# Head_Lamp.net
KiCad netlist of a schematic drawn in EAGLE
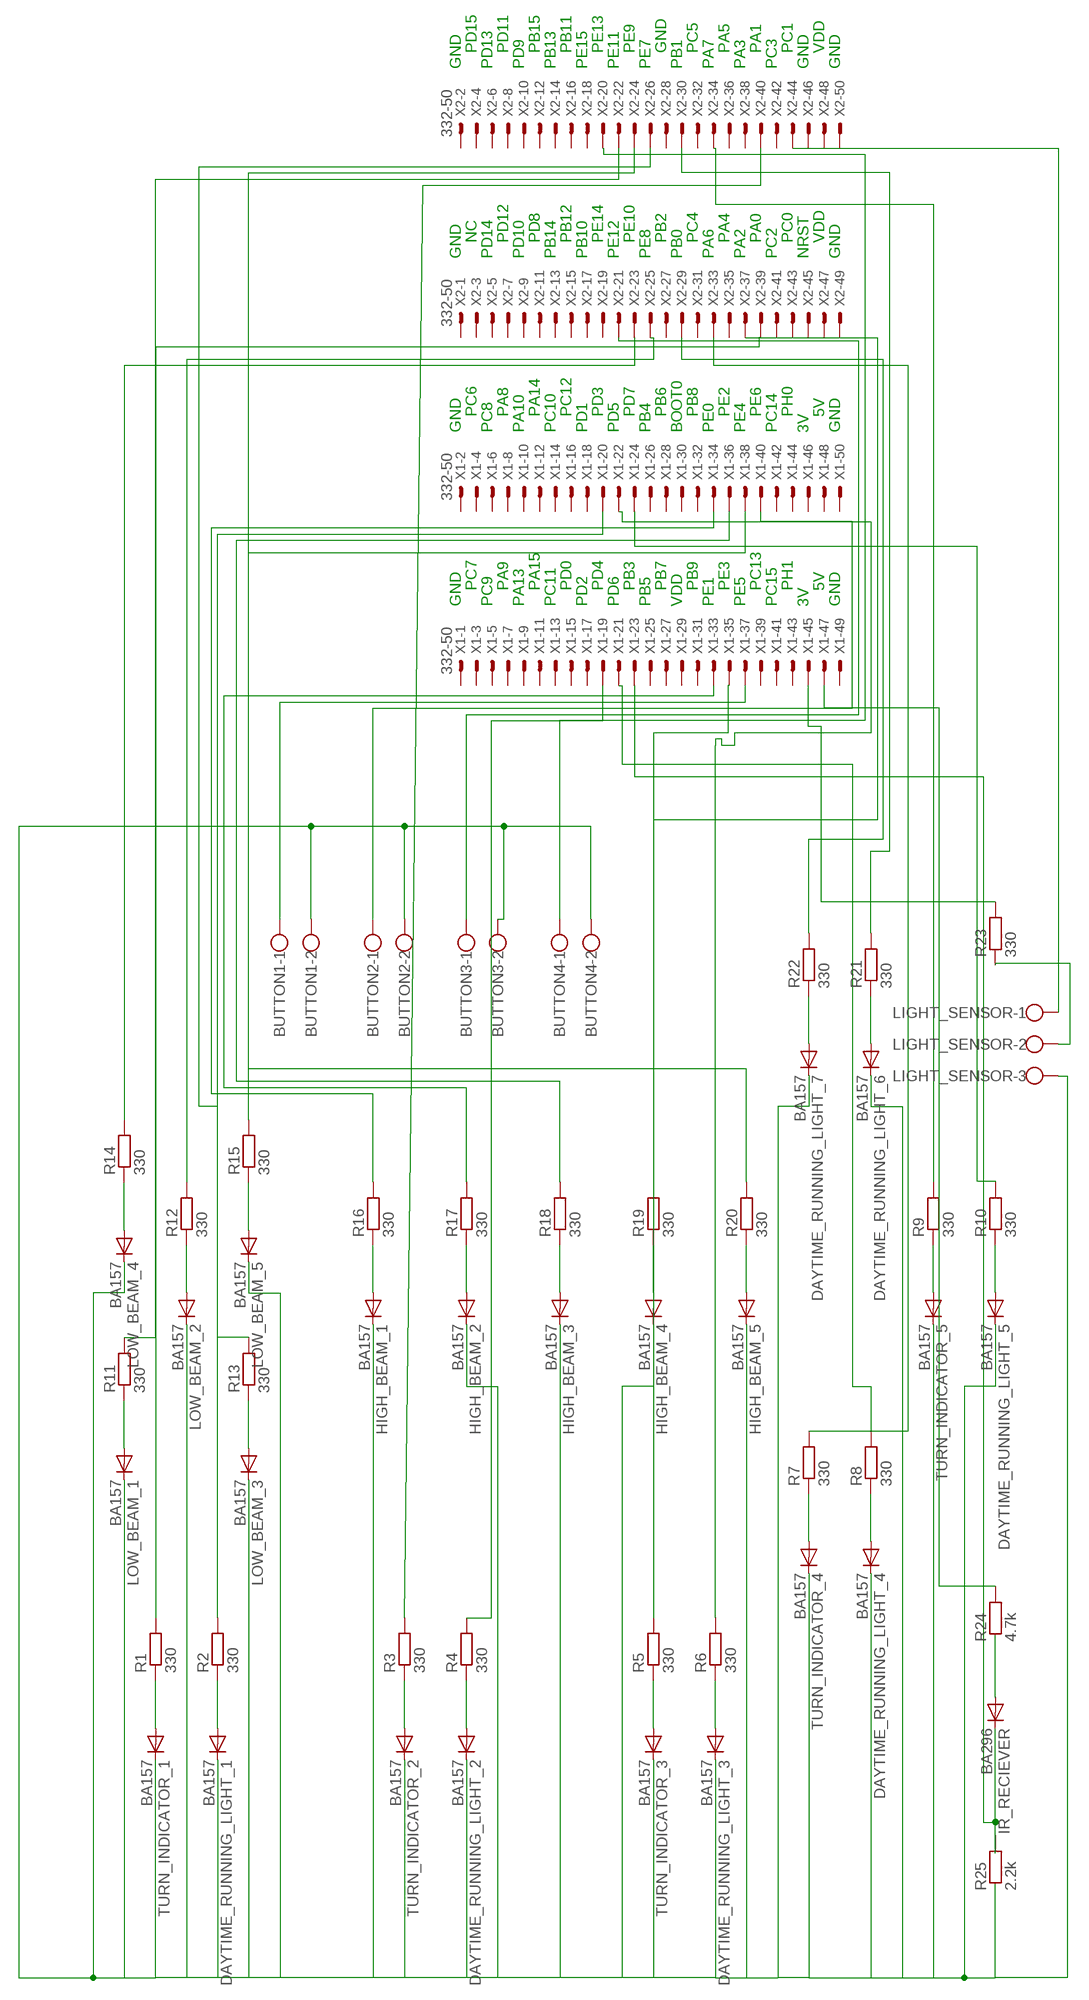
[diagram p0: schematic, sheet 1]

(export (version "E")
  (design (tool "Eeschema 10.0.6"))
  (components
    (comp (ref "BUTTON1")
      (value "W237-102")
      (footprint "eagle-import:W237-102")
      (fields (field (name "MPN") "237-102"))
      (libsource (lib "eagle-import") (part "W237-102"))
    )
    (comp (ref "BUTTON2")
      (value "W237-102")
      (footprint "eagle-import:W237-102")
      (fields (field (name "MPN") "237-102"))
      (libsource (lib "eagle-import") (part "W237-102"))
    )
    (comp (ref "BUTTON3")
      (value "W237-102")
      (footprint "eagle-import:W237-102")
      (fields (field (name "MPN") "237-102"))
      (libsource (lib "eagle-import") (part "W237-102"))
    )
    (comp (ref "BUTTON4")
      (value "W237-102")
      (footprint "eagle-import:W237-102")
      (fields (field (name "MPN") "237-102"))
      (libsource (lib "eagle-import") (part "W237-102"))
    )
    (comp (ref "DAYTIME_RUNNING_LIGHT_1")
      (value "BA157")
      (footprint "eagle-import:P1-10")
      (libsource (lib "eagle-import") (part "BA157"))
    )
    (comp (ref "DAYTIME_RUNNING_LIGHT_2")
      (value "BA157")
      (footprint "eagle-import:P1-10")
      (libsource (lib "eagle-import") (part "BA157"))
    )
    (comp (ref "DAYTIME_RUNNING_LIGHT_3")
      (value "BA157")
      (footprint "eagle-import:P1-10")
      (libsource (lib "eagle-import") (part "BA157"))
    )
    (comp (ref "DAYTIME_RUNNING_LIGHT_4")
      (value "BA157")
      (footprint "eagle-import:P1-10")
      (libsource (lib "eagle-import") (part "BA157"))
    )
    (comp (ref "DAYTIME_RUNNING_LIGHT_5")
      (value "BA157")
      (footprint "eagle-import:P1-10")
      (libsource (lib "eagle-import") (part "BA157"))
    )
    (comp (ref "DAYTIME_RUNNING_LIGHT_6")
      (value "BA157")
      (footprint "eagle-import:P1-10")
      (libsource (lib "eagle-import") (part "BA157"))
    )
    (comp (ref "DAYTIME_RUNNING_LIGHT_7")
      (value "BA157")
      (footprint "eagle-import:P1-10")
      (libsource (lib "eagle-import") (part "BA157"))
    )
    (comp (ref "HIGH_BEAM_1")
      (value "BA157")
      (footprint "eagle-import:P1-10")
      (libsource (lib "eagle-import") (part "BA157"))
    )
    (comp (ref "HIGH_BEAM_2")
      (value "BA157")
      (footprint "eagle-import:P1-10")
      (libsource (lib "eagle-import") (part "BA157"))
    )
    (comp (ref "HIGH_BEAM_3")
      (value "BA157")
      (footprint "eagle-import:P1-10")
      (libsource (lib "eagle-import") (part "BA157"))
    )
    (comp (ref "HIGH_BEAM_4")
      (value "BA157")
      (footprint "eagle-import:P1-10")
      (libsource (lib "eagle-import") (part "BA157"))
    )
    (comp (ref "HIGH_BEAM_5")
      (value "BA157")
      (footprint "eagle-import:P1-10")
      (libsource (lib "eagle-import") (part "BA157"))
    )
    (comp (ref "IR_RECIEVER")
      (value "BA296")
      (footprint "eagle-import:P2-15")
      (libsource (lib "eagle-import") (part "BA296"))
    )
    (comp (ref "LIGHT_SENSOR")
      (value "W237-103")
      (footprint "eagle-import:W237-103")
      (fields (field (name "MPN") "237-103"))
      (libsource (lib "eagle-import") (part "W237-103"))
    )
    (comp (ref "LOW_BEAM_1")
      (value "BA157")
      (footprint "eagle-import:P1-10")
      (libsource (lib "eagle-import") (part "BA157"))
    )
    (comp (ref "LOW_BEAM_2")
      (value "BA157")
      (footprint "eagle-import:P1-10")
      (libsource (lib "eagle-import") (part "BA157"))
    )
    (comp (ref "LOW_BEAM_3")
      (value "BA157")
      (footprint "eagle-import:P1-10")
      (libsource (lib "eagle-import") (part "BA157"))
    )
    (comp (ref "LOW_BEAM_4")
      (value "BA157")
      (footprint "eagle-import:P1-10")
      (libsource (lib "eagle-import") (part "BA157"))
    )
    (comp (ref "LOW_BEAM_5")
      (value "BA157")
      (footprint "eagle-import:P1-10")
      (libsource (lib "eagle-import") (part "BA157"))
    )
    (comp (ref "R1")
      (value "330")
      (footprint "eagle-import:0204_7")
      (libsource (lib "eagle-import") (part "R0204/7"))
    )
    (comp (ref "R2")
      (value "330")
      (footprint "eagle-import:0204_7")
      (libsource (lib "eagle-import") (part "R0204/7"))
    )
    (comp (ref "R3")
      (value "330")
      (footprint "eagle-import:0204_7")
      (libsource (lib "eagle-import") (part "R0204/7"))
    )
    (comp (ref "R4")
      (value "330")
      (footprint "eagle-import:0204_7")
      (libsource (lib "eagle-import") (part "R0204/7"))
    )
    (comp (ref "R5")
      (value "330")
      (footprint "eagle-import:0204_7")
      (libsource (lib "eagle-import") (part "R0204/7"))
    )
    (comp (ref "R6")
      (value "330")
      (footprint "eagle-import:0204_7")
      (libsource (lib "eagle-import") (part "R0204/7"))
    )
    (comp (ref "R7")
      (value "330")
      (footprint "eagle-import:0204_7")
      (libsource (lib "eagle-import") (part "R0204/7"))
    )
    (comp (ref "R8")
      (value "330")
      (footprint "eagle-import:0204_7")
      (libsource (lib "eagle-import") (part "R0204/7"))
    )
    (comp (ref "R9")
      (value "330")
      (footprint "eagle-import:0204_7")
      (libsource (lib "eagle-import") (part "R0204/7"))
    )
    (comp (ref "R10")
      (value "330")
      (footprint "eagle-import:0204_7")
      (libsource (lib "eagle-import") (part "R0204/7"))
    )
    (comp (ref "R11")
      (value "330")
      (footprint "eagle-import:0204_7")
      (libsource (lib "eagle-import") (part "R0204/7"))
    )
    (comp (ref "R12")
      (value "330")
      (footprint "eagle-import:0204_7")
      (libsource (lib "eagle-import") (part "R0204/7"))
    )
    (comp (ref "R13")
      (value "330")
      (footprint "eagle-import:0204_7")
      (libsource (lib "eagle-import") (part "R0204/7"))
    )
    (comp (ref "R14")
      (value "330")
      (footprint "eagle-import:0204_7")
      (libsource (lib "eagle-import") (part "R0204/7"))
    )
    (comp (ref "R15")
      (value "330")
      (footprint "eagle-import:0204_7")
      (libsource (lib "eagle-import") (part "R0204/7"))
    )
    (comp (ref "R16")
      (value "330")
      (footprint "eagle-import:0204_7")
      (libsource (lib "eagle-import") (part "R0204/7"))
    )
    (comp (ref "R17")
      (value "330")
      (footprint "eagle-import:0204_7")
      (libsource (lib "eagle-import") (part "R0204/7"))
    )
    (comp (ref "R18")
      (value "330")
      (footprint "eagle-import:0204_7")
      (libsource (lib "eagle-import") (part "R0204/7"))
    )
    (comp (ref "R19")
      (value "330")
      (footprint "eagle-import:0204_7")
      (libsource (lib "eagle-import") (part "R0204/7"))
    )
    (comp (ref "R20")
      (value "330")
      (footprint "eagle-import:0204_7")
      (libsource (lib "eagle-import") (part "R0204/7"))
    )
    (comp (ref "R21")
      (value "330")
      (footprint "eagle-import:0204_7")
      (libsource (lib "eagle-import") (part "R0204/7"))
    )
    (comp (ref "R22")
      (value "330")
      (footprint "eagle-import:0204_7")
      (libsource (lib "eagle-import") (part "R0204/7"))
    )
    (comp (ref "R23")
      (value "330")
      (footprint "eagle-import:0204_7")
      (libsource (lib "eagle-import") (part "R0204/7"))
    )
    (comp (ref "R24")
      (value "4.7k")
      (footprint "eagle-import:0204_7")
      (libsource (lib "eagle-import") (part "R0204/7"))
    )
    (comp (ref "R25")
      (value "2.2k")
      (footprint "eagle-import:0204_7")
      (libsource (lib "eagle-import") (part "R0204/7"))
    )
    (comp (ref "TURN_INDICATOR_1")
      (value "BA157")
      (footprint "eagle-import:P1-10")
      (libsource (lib "eagle-import") (part "BA157"))
    )
    (comp (ref "TURN_INDICATOR_2")
      (value "BA157")
      (footprint "eagle-import:P1-10")
      (libsource (lib "eagle-import") (part "BA157"))
    )
    (comp (ref "TURN_INDICATOR_3")
      (value "BA157")
      (footprint "eagle-import:P1-10")
      (libsource (lib "eagle-import") (part "BA157"))
    )
    (comp (ref "TURN_INDICATOR_4")
      (value "BA157")
      (footprint "eagle-import:P1-10")
      (libsource (lib "eagle-import") (part "BA157"))
    )
    (comp (ref "TURN_INDICATOR_5")
      (value "BA157")
      (footprint "eagle-import:P1-10")
      (libsource (lib "eagle-import") (part "BA157"))
    )
    (comp (ref "X1")
      (value "332-50")
      (footprint "eagle-import:332-50")
      (libsource (lib "eagle-import") (part "332-50"))
    )
    (comp (ref "X2")
      (value "332-50")
      (footprint "eagle-import:332-50")
      (libsource (lib "eagle-import") (part "332-50"))
    )
  )
  (nets
    (net (code "1") (name "Net-(BUTTON1A-KL)") (class "Default")
      (node (ref "BUTTON1") (pin "1") (pinfunction "KL_1") (pintype "passive"))
      (node (ref "X1") (pin "37") (pinfunction "S_37") (pintype "passive"))
    )
    (net (code "2") (name "Net-(BUTTON1B-KL)") (class "Default")
      (node (ref "BUTTON1") (pin "2") (pinfunction "KL_2") (pintype "passive"))
      (node (ref "BUTTON2") (pin "2") (pinfunction "KL_2") (pintype "passive"))
      (node (ref "BUTTON3") (pin "2") (pinfunction "KL_2") (pintype "passive"))
      (node (ref "BUTTON4") (pin "2") (pinfunction "KL_2") (pintype "passive"))
      (node (ref "DAYTIME_RUNNING_LIGHT_1") (pin "C") (pinfunction "C_C") (pintype "passive"))
      (node (ref "DAYTIME_RUNNING_LIGHT_2") (pin "C") (pinfunction "C_C") (pintype "passive"))
      (node (ref "DAYTIME_RUNNING_LIGHT_3") (pin "C") (pinfunction "C_C") (pintype "passive"))
      (node (ref "DAYTIME_RUNNING_LIGHT_4") (pin "C") (pinfunction "C_C") (pintype "passive"))
      (node (ref "DAYTIME_RUNNING_LIGHT_5") (pin "C") (pinfunction "C_C") (pintype "passive"))
      (node (ref "DAYTIME_RUNNING_LIGHT_6") (pin "C") (pinfunction "C_C") (pintype "passive"))
      (node (ref "DAYTIME_RUNNING_LIGHT_7") (pin "C") (pinfunction "C_C") (pintype "passive"))
      (node (ref "HIGH_BEAM_1") (pin "C") (pinfunction "C_C") (pintype "passive"))
      (node (ref "HIGH_BEAM_2") (pin "C") (pinfunction "C_C") (pintype "passive"))
      (node (ref "HIGH_BEAM_3") (pin "C") (pinfunction "C_C") (pintype "passive"))
      (node (ref "HIGH_BEAM_4") (pin "C") (pinfunction "C_C") (pintype "passive"))
      (node (ref "HIGH_BEAM_5") (pin "C") (pinfunction "C_C") (pintype "passive"))
      (node (ref "LIGHT_SENSOR") (pin "3") (pinfunction "KL_3") (pintype "passive"))
      (node (ref "LOW_BEAM_1") (pin "C") (pinfunction "C_C") (pintype "passive"))
      (node (ref "LOW_BEAM_2") (pin "C") (pinfunction "C_C") (pintype "passive"))
      (node (ref "LOW_BEAM_3") (pin "C") (pinfunction "C_C") (pintype "passive"))
      (node (ref "LOW_BEAM_4") (pin "C") (pinfunction "C_C") (pintype "passive"))
      (node (ref "LOW_BEAM_5") (pin "C") (pinfunction "C_C") (pintype "passive"))
      (node (ref "TURN_INDICATOR_1") (pin "C") (pinfunction "C_C") (pintype "passive"))
      (node (ref "TURN_INDICATOR_2") (pin "C") (pinfunction "C_C") (pintype "passive"))
      (node (ref "TURN_INDICATOR_3") (pin "C") (pinfunction "C_C") (pintype "passive"))
      (node (ref "TURN_INDICATOR_4") (pin "C") (pinfunction "C_C") (pintype "passive"))
      (node (ref "TURN_INDICATOR_5") (pin "C") (pinfunction "C_C") (pintype "passive"))
    )
    (net (code "3") (name "Net-(BUTTON2A-KL)") (class "Default")
      (node (ref "BUTTON2") (pin "1") (pinfunction "KL_1") (pintype "passive"))
      (node (ref "X1") (pin "40") (pinfunction "S_40") (pintype "passive"))
    )
    (net (code "4") (name "Net-(BUTTON3A-KL)") (class "Default")
      (node (ref "BUTTON3") (pin "1") (pinfunction "KL_1") (pintype "passive"))
      (node (ref "X2") (pin "21") (pinfunction "S_21") (pintype "passive"))
    )
    (net (code "5") (name "Net-(BUTTON4A-KL)") (class "Default")
      (node (ref "BUTTON4") (pin "1") (pinfunction "KL_1") (pintype "passive"))
      (node (ref "X2") (pin "20") (pinfunction "S_20") (pintype "passive"))
    )
    (net (code "6") (name "Net-(DAYTIME_RUNNING_LIGHT_1-PadA)") (class "Default")
      (node (ref "DAYTIME_RUNNING_LIGHT_1") (pin "A") (pinfunction "A_A") (pintype "passive"))
      (node (ref "R2") (pin "1") (pinfunction "1_1") (pintype "passive"))
    )
    (net (code "7") (name "Net-(DAYTIME_RUNNING_LIGHT_2-PadA)") (class "Default")
      (node (ref "DAYTIME_RUNNING_LIGHT_2") (pin "A") (pinfunction "A_A") (pintype "passive"))
      (node (ref "R4") (pin "1") (pinfunction "1_1") (pintype "passive"))
    )
    (net (code "8") (name "Net-(DAYTIME_RUNNING_LIGHT_3-PadA)") (class "Default")
      (node (ref "DAYTIME_RUNNING_LIGHT_3") (pin "A") (pinfunction "A_A") (pintype "passive"))
      (node (ref "R6") (pin "1") (pinfunction "1_1") (pintype "passive"))
    )
    (net (code "9") (name "Net-(DAYTIME_RUNNING_LIGHT_4-PadA)") (class "Default")
      (node (ref "DAYTIME_RUNNING_LIGHT_4") (pin "A") (pinfunction "A_A") (pintype "passive"))
      (node (ref "R8") (pin "1") (pinfunction "1_1") (pintype "passive"))
    )
    (net (code "10") (name "Net-(DAYTIME_RUNNING_LIGHT_5-PadA)") (class "Default")
      (node (ref "DAYTIME_RUNNING_LIGHT_5") (pin "A") (pinfunction "A_A") (pintype "passive"))
      (node (ref "R10") (pin "1") (pinfunction "1_1") (pintype "passive"))
    )
    (net (code "11") (name "Net-(DAYTIME_RUNNING_LIGHT_6-PadA)") (class "Default")
      (node (ref "DAYTIME_RUNNING_LIGHT_6") (pin "A") (pinfunction "A_A") (pintype "passive"))
      (node (ref "R21") (pin "1") (pinfunction "1_1") (pintype "passive"))
    )
    (net (code "12") (name "Net-(DAYTIME_RUNNING_LIGHT_7-PadA)") (class "Default")
      (node (ref "DAYTIME_RUNNING_LIGHT_7") (pin "A") (pinfunction "A_A") (pintype "passive"))
      (node (ref "R22") (pin "1") (pinfunction "1_1") (pintype "passive"))
    )
    (net (code "13") (name "Net-(HIGH_BEAM_1-PadA)") (class "Default")
      (node (ref "HIGH_BEAM_1") (pin "A") (pinfunction "A_A") (pintype "passive"))
      (node (ref "R16") (pin "1") (pinfunction "1_1") (pintype "passive"))
    )
    (net (code "14") (name "Net-(HIGH_BEAM_2-PadA)") (class "Default")
      (node (ref "HIGH_BEAM_2") (pin "A") (pinfunction "A_A") (pintype "passive"))
      (node (ref "R17") (pin "1") (pinfunction "1_1") (pintype "passive"))
    )
    (net (code "15") (name "Net-(HIGH_BEAM_3-PadA)") (class "Default")
      (node (ref "HIGH_BEAM_3") (pin "A") (pinfunction "A_A") (pintype "passive"))
      (node (ref "R18") (pin "1") (pinfunction "1_1") (pintype "passive"))
    )
    (net (code "16") (name "Net-(HIGH_BEAM_4-PadA)") (class "Default")
      (node (ref "HIGH_BEAM_4") (pin "A") (pinfunction "A_A") (pintype "passive"))
      (node (ref "R19") (pin "1") (pinfunction "1_1") (pintype "passive"))
    )
    (net (code "17") (name "Net-(HIGH_BEAM_5-PadA)") (class "Default")
      (node (ref "HIGH_BEAM_5") (pin "A") (pinfunction "A_A") (pintype "passive"))
      (node (ref "R20") (pin "1") (pinfunction "1_1") (pintype "passive"))
    )
    (net (code "18") (name "Net-(LIGHT_SENSORA-KL)") (class "Default")
      (node (ref "LIGHT_SENSOR") (pin "1") (pinfunction "KL_1") (pintype "passive"))
      (node (ref "X2") (pin "44") (pinfunction "S_44") (pintype "passive"))
    )
    (net (code "19") (name "Net-(LIGHT_SENSORB-KL)") (class "Default")
      (node (ref "LIGHT_SENSOR") (pin "2") (pinfunction "KL_2") (pintype "passive"))
      (node (ref "R23") (pin "1") (pinfunction "1_1") (pintype "passive"))
    )
    (net (code "20") (name "Net-(LOW_BEAM_1-PadA)") (class "Default")
      (node (ref "LOW_BEAM_1") (pin "A") (pinfunction "A_A") (pintype "passive"))
      (node (ref "R11") (pin "1") (pinfunction "1_1") (pintype "passive"))
    )
    (net (code "21") (name "Net-(LOW_BEAM_2-PadA)") (class "Default")
      (node (ref "LOW_BEAM_2") (pin "A") (pinfunction "A_A") (pintype "passive"))
      (node (ref "R12") (pin "1") (pinfunction "1_1") (pintype "passive"))
    )
    (net (code "22") (name "Net-(LOW_BEAM_3-PadA)") (class "Default")
      (node (ref "LOW_BEAM_3") (pin "A") (pinfunction "A_A") (pintype "passive"))
      (node (ref "R13") (pin "1") (pinfunction "1_1") (pintype "passive"))
    )
    (net (code "23") (name "Net-(LOW_BEAM_4-PadA)") (class "Default")
      (node (ref "LOW_BEAM_4") (pin "A") (pinfunction "A_A") (pintype "passive"))
      (node (ref "R14") (pin "1") (pinfunction "1_1") (pintype "passive"))
    )
    (net (code "24") (name "Net-(LOW_BEAM_5-PadA)") (class "Default")
      (node (ref "LOW_BEAM_5") (pin "A") (pinfunction "A_A") (pintype "passive"))
      (node (ref "R15") (pin "1") (pinfunction "1_1") (pintype "passive"))
    )
    (net (code "25") (name "Net-(R1-Pad1)") (class "Default")
      (node (ref "R1") (pin "1") (pinfunction "1_1") (pintype "passive"))
      (node (ref "TURN_INDICATOR_1") (pin "A") (pinfunction "A_A") (pintype "passive"))
    )
    (net (code "26") (name "Net-(R3-Pad1)") (class "Default")
      (node (ref "R3") (pin "1") (pinfunction "1_1") (pintype "passive"))
      (node (ref "TURN_INDICATOR_2") (pin "A") (pinfunction "A_A") (pintype "passive"))
    )
    (net (code "27") (name "Net-(R5-Pad1)") (class "Default")
      (node (ref "R5") (pin "1") (pinfunction "1_1") (pintype "passive"))
      (node (ref "TURN_INDICATOR_3") (pin "A") (pinfunction "A_A") (pintype "passive"))
    )
    (net (code "28") (name "Net-(R7-Pad1)") (class "Default")
      (node (ref "R7") (pin "1") (pinfunction "1_1") (pintype "passive"))
      (node (ref "TURN_INDICATOR_4") (pin "A") (pinfunction "A_A") (pintype "passive"))
    )
    (net (code "29") (name "Net-(R9-Pad1)") (class "Default")
      (node (ref "R9") (pin "1") (pinfunction "1_1") (pintype "passive"))
      (node (ref "TURN_INDICATOR_5") (pin "A") (pinfunction "A_A") (pintype "passive"))
    )
    (net (code "30") (name "Net-(X1AA-S)") (class "Default")
      (node (ref "R17") (pin "2") (pinfunction "2_2") (pintype "passive"))
      (node (ref "X1") (pin "33") (pinfunction "S_33") (pintype "passive"))
    )
    (net (code "31") (name "Net-(X1AB-S)") (class "Default")
      (node (ref "R16") (pin "2") (pinfunction "2_2") (pintype "passive"))
      (node (ref "X1") (pin "34") (pinfunction "S_34") (pintype "passive"))
    )
    (net (code "32") (name "Net-(X1AC-S)") (class "Default")
      (node (ref "R19") (pin "2") (pinfunction "2_2") (pintype "passive"))
      (node (ref "X1") (pin "35") (pinfunction "S_35") (pintype "passive"))
    )
    (net (code "33") (name "Net-(X1AD-S)") (class "Default")
      (node (ref "R18") (pin "2") (pinfunction "2_2") (pintype "passive"))
      (node (ref "X1") (pin "36") (pinfunction "S_36") (pintype "passive"))
    )
    (net (code "34") (name "Net-(X1AF-S)") (class "Default")
      (node (ref "R20") (pin "2") (pinfunction "2_2") (pintype "passive"))
      (node (ref "X1") (pin "38") (pinfunction "S_38") (pintype "passive"))
    )
    (net (code "35") (name "Net-(X1AN-S)") (class "Default")
      (node (ref "R23") (pin "2") (pinfunction "2_2") (pintype "passive"))
      (node (ref "X1") (pin "45") (pinfunction "S_45") (pintype "passive"))
    )
    (net (code "36") (name "Net-(X1AP-S)") (class "Default")
      (node (ref "R24") (pin "2") (pinfunction "2_2") (pintype "passive"))
      (node (ref "X1") (pin "47") (pinfunction "S_47") (pintype "passive"))
    )
    (net (code "37") (name "Net-(X1K-S)") (class "Default")
      (node (ref "R4") (pin "2") (pinfunction "2_2") (pintype "passive"))
      (node (ref "X1") (pin "19") (pinfunction "S_19") (pintype "passive"))
    )
    (net (code "38") (name "Net-(X1M-S)") (class "Default")
      (node (ref "R2") (pin "2") (pinfunction "2_2") (pintype "passive"))
      (node (ref "X1") (pin "20") (pinfunction "S_20") (pintype "passive"))
    )
    (net (code "39") (name "Net-(X1N-S)") (class "Default")
      (node (ref "R8") (pin "2") (pinfunction "2_2") (pintype "passive"))
      (node (ref "X1") (pin "21") (pinfunction "S_21") (pintype "passive"))
    )
    (net (code "40") (name "Net-(X1O-S)") (class "Default")
      (node (ref "R6") (pin "2") (pinfunction "2_2") (pintype "passive"))
      (node (ref "X1") (pin "22") (pinfunction "S_22") (pintype "passive"))
    )
    (net (code "41") (name "Net-(X1Q-S)") (class "Default")
      (node (ref "R10") (pin "2") (pinfunction "2_2") (pintype "passive"))
      (node (ref "X1") (pin "24") (pinfunction "S_24") (pintype "passive"))
    )
    (net (code "42") (name "Net-(X2AA-S)") (class "Default")
      (node (ref "R7") (pin "2") (pinfunction "2_2") (pintype "passive"))
      (node (ref "X2") (pin "33") (pinfunction "S_33") (pintype "passive"))
    )
    (net (code "43") (name "Net-(X2AB-S)") (class "Default")
      (node (ref "R9") (pin "2") (pinfunction "2_2") (pintype "passive"))
      (node (ref "X2") (pin "34") (pinfunction "S_34") (pintype "passive"))
    )
    (net (code "44") (name "Net-(X2AE-S)") (class "Default")
      (node (ref "R5") (pin "2") (pinfunction "2_2") (pintype "passive"))
      (node (ref "X2") (pin "37") (pinfunction "S_37") (pintype "passive"))
    )
    (net (code "45") (name "Net-(X2AG-S)") (class "Default")
      (node (ref "R1") (pin "2") (pinfunction "2_2") (pintype "passive"))
      (node (ref "X2") (pin "39") (pinfunction "S_39") (pintype "passive"))
    )
    (net (code "46") (name "Net-(X2AI-S)") (class "Default")
      (node (ref "R3") (pin "2") (pinfunction "2_2") (pintype "passive"))
      (node (ref "X2") (pin "40") (pinfunction "S_40") (pintype "passive"))
    )
    (net (code "47") (name "Net-(X2O-S)") (class "Default")
      (node (ref "R11") (pin "2") (pinfunction "2_2") (pintype "passive"))
      (node (ref "X2") (pin "22") (pinfunction "S_22") (pintype "passive"))
    )
    (net (code "48") (name "Net-(X2P-S)") (class "Default")
      (node (ref "R14") (pin "2") (pinfunction "2_2") (pintype "passive"))
      (node (ref "X2") (pin "23") (pinfunction "S_23") (pintype "passive"))
    )
    (net (code "49") (name "Net-(X2Q-S)") (class "Default")
      (node (ref "R15") (pin "2") (pinfunction "2_2") (pintype "passive"))
      (node (ref "X2") (pin "24") (pinfunction "S_24") (pintype "passive"))
    )
    (net (code "50") (name "Net-(X2R-S)") (class "Default")
      (node (ref "R12") (pin "2") (pinfunction "2_2") (pintype "passive"))
      (node (ref "X2") (pin "25") (pinfunction "S_25") (pintype "passive"))
    )
    (net (code "51") (name "Net-(X2S-S)") (class "Default")
      (node (ref "R13") (pin "2") (pinfunction "2_2") (pintype "passive"))
      (node (ref "X2") (pin "26") (pinfunction "S_26") (pintype "passive"))
    )
    (net (code "52") (name "Net-(X2V-S)") (class "Default")
      (node (ref "R22") (pin "2") (pinfunction "2_2") (pintype "passive"))
      (node (ref "X2") (pin "29") (pinfunction "S_29") (pintype "passive"))
    )
    (net (code "53") (name "Net-(X2X-S)") (class "Default")
      (node (ref "R21") (pin "2") (pinfunction "2_2") (pintype "passive"))
      (node (ref "X2") (pin "30") (pinfunction "S_30") (pintype "passive"))
    )
    (net (code "54") (name "unconnected-(IR_RECIEVER-PadA)") (class "Default")
      (node (ref "IR_RECIEVER") (pin "A") (pinfunction "A_A") (pintype "passive"))
    )
    (net (code "55") (name "unconnected-(IR_RECIEVER-PadC)") (class "Default")
      (node (ref "IR_RECIEVER") (pin "C") (pinfunction "C_C") (pintype "passive"))
    )
    (net (code "56") (name "unconnected-(R24-Pad1)") (class "Default")
      (node (ref "R24") (pin "1") (pinfunction "1_1") (pintype "passive"))
    )
    (net (code "57") (name "unconnected-(R25-Pad1)") (class "Default")
      (node (ref "R25") (pin "1") (pinfunction "1_1") (pintype "passive"))
    )
    (net (code "58") (name "unconnected-(R25-Pad2)") (class "Default")
      (node (ref "R25") (pin "2") (pinfunction "2_2") (pintype "passive"))
    )
    (net (code "59") (name "unconnected-(X1A-S-Pad1)") (class "Default")
      (node (ref "X1") (pin "1") (pinfunction "S_1") (pintype "passive"))
    )
    (net (code "60") (name "unconnected-(X1AG-S-Pad39)") (class "Default")
      (node (ref "X1") (pin "39") (pinfunction "S_39") (pintype "passive"))
    )
    (net (code "61") (name "unconnected-(X1AH-S-Pad4)") (class "Default")
      (node (ref "X1") (pin "4") (pinfunction "S_4") (pintype "passive"))
    )
    (net (code "62") (name "unconnected-(X1AJ-S-Pad41)") (class "Default")
      (node (ref "X1") (pin "41") (pinfunction "S_41") (pintype "passive"))
    )
    (net (code "63") (name "unconnected-(X1AK-S-Pad42)") (class "Default")
      (node (ref "X1") (pin "42") (pinfunction "S_42") (pintype "passive"))
    )
    (net (code "64") (name "unconnected-(X1AL-S-Pad43)") (class "Default")
      (node (ref "X1") (pin "43") (pinfunction "S_43") (pintype "passive"))
    )
    (net (code "65") (name "unconnected-(X1AM-S-Pad44)") (class "Default")
      (node (ref "X1") (pin "44") (pinfunction "S_44") (pintype "passive"))
    )
    (net (code "66") (name "unconnected-(X1AO-S-Pad46)") (class "Default")
      (node (ref "X1") (pin "46") (pinfunction "S_46") (pintype "passive"))
    )
    (net (code "67") (name "unconnected-(X1AQ-S-Pad48)") (class "Default")
      (node (ref "X1") (pin "48") (pinfunction "S_48") (pintype "passive"))
    )
    (net (code "68") (name "unconnected-(X1AR-S-Pad49)") (class "Default")
      (node (ref "X1") (pin "49") (pinfunction "S_49") (pintype "passive"))
    )
    (net (code "69") (name "unconnected-(X1AS-S-Pad5)") (class "Default")
      (node (ref "X1") (pin "5") (pinfunction "S_5") (pintype "passive"))
    )
    (net (code "70") (name "unconnected-(X1AT-S-Pad50)") (class "Default")
      (node (ref "X1") (pin "50") (pinfunction "S_50") (pintype "passive"))
    )
    (net (code "71") (name "unconnected-(X1AU-S-Pad6)") (class "Default")
      (node (ref "X1") (pin "6") (pinfunction "S_6") (pintype "passive"))
    )
    (net (code "72") (name "unconnected-(X1AV-S-Pad7)") (class "Default")
      (node (ref "X1") (pin "7") (pinfunction "S_7") (pintype "passive"))
    )
    (net (code "73") (name "unconnected-(X1AW-S-Pad8)") (class "Default")
      (node (ref "X1") (pin "8") (pinfunction "S_8") (pintype "passive"))
    )
    (net (code "74") (name "unconnected-(X1AX-S-Pad9)") (class "Default")
      (node (ref "X1") (pin "9") (pinfunction "S_9") (pintype "passive"))
    )
    (net (code "75") (name "unconnected-(X1B-S-Pad10)") (class "Default")
      (node (ref "X1") (pin "10") (pinfunction "S_10") (pintype "passive"))
    )
    (net (code "76") (name "unconnected-(X1C-S-Pad11)") (class "Default")
      (node (ref "X1") (pin "11") (pinfunction "S_11") (pintype "passive"))
    )
    (net (code "77") (name "unconnected-(X1D-S-Pad12)") (class "Default")
      (node (ref "X1") (pin "12") (pinfunction "S_12") (pintype "passive"))
    )
    (net (code "78") (name "unconnected-(X1E-S-Pad13)") (class "Default")
      (node (ref "X1") (pin "13") (pinfunction "S_13") (pintype "passive"))
    )
    (net (code "79") (name "unconnected-(X1F-S-Pad14)") (class "Default")
      (node (ref "X1") (pin "14") (pinfunction "S_14") (pintype "passive"))
    )
    (net (code "80") (name "unconnected-(X1G-S-Pad15)") (class "Default")
      (node (ref "X1") (pin "15") (pinfunction "S_15") (pintype "passive"))
    )
    (net (code "81") (name "unconnected-(X1H-S-Pad16)") (class "Default")
      (node (ref "X1") (pin "16") (pinfunction "S_16") (pintype "passive"))
    )
    (net (code "82") (name "unconnected-(X1I-S-Pad17)") (class "Default")
      (node (ref "X1") (pin "17") (pinfunction "S_17") (pintype "passive"))
    )
    (net (code "83") (name "unconnected-(X1J-S-Pad18)") (class "Default")
      (node (ref "X1") (pin "18") (pinfunction "S_18") (pintype "passive"))
    )
    (net (code "84") (name "unconnected-(X1L-S-Pad2)") (class "Default")
      (node (ref "X1") (pin "2") (pinfunction "S_2") (pintype "passive"))
    )
    (net (code "85") (name "unconnected-(X1P-S-Pad23)") (class "Default")
      (node (ref "X1") (pin "23") (pinfunction "S_23") (pintype "passive"))
    )
    (net (code "86") (name "unconnected-(X1R-S-Pad25)") (class "Default")
      (node (ref "X1") (pin "25") (pinfunction "S_25") (pintype "passive"))
    )
    (net (code "87") (name "unconnected-(X1S-S-Pad26)") (class "Default")
      (node (ref "X1") (pin "26") (pinfunction "S_26") (pintype "passive"))
    )
    (net (code "88") (name "unconnected-(X1T-S-Pad27)") (class "Default")
      (node (ref "X1") (pin "27") (pinfunction "S_27") (pintype "passive"))
    )
    (net (code "89") (name "unconnected-(X1U-S-Pad28)") (class "Default")
      (node (ref "X1") (pin "28") (pinfunction "S_28") (pintype "passive"))
    )
    (net (code "90") (name "unconnected-(X1V-S-Pad29)") (class "Default")
      (node (ref "X1") (pin "29") (pinfunction "S_29") (pintype "passive"))
    )
    (net (code "91") (name "unconnected-(X1W-S-Pad3)") (class "Default")
      (node (ref "X1") (pin "3") (pinfunction "S_3") (pintype "passive"))
    )
    (net (code "92") (name "unconnected-(X1X-S-Pad30)") (class "Default")
      (node (ref "X1") (pin "30") (pinfunction "S_30") (pintype "passive"))
    )
    (net (code "93") (name "unconnected-(X1Y-S-Pad31)") (class "Default")
      (node (ref "X1") (pin "31") (pinfunction "S_31") (pintype "passive"))
    )
    (net (code "94") (name "unconnected-(X1Z-S-Pad32)") (class "Default")
      (node (ref "X1") (pin "32") (pinfunction "S_32") (pintype "passive"))
    )
    (net (code "95") (name "unconnected-(X2A-S-Pad1)") (class "Default")
      (node (ref "X2") (pin "1") (pinfunction "S_1") (pintype "passive"))
    )
    (net (code "96") (name "unconnected-(X2AC-S-Pad35)") (class "Default")
      (node (ref "X2") (pin "35") (pinfunction "S_35") (pintype "passive"))
    )
    (net (code "97") (name "unconnected-(X2AD-S-Pad36)") (class "Default")
      (node (ref "X2") (pin "36") (pinfunction "S_36") (pintype "passive"))
    )
    (net (code "98") (name "unconnected-(X2AF-S-Pad38)") (class "Default")
      (node (ref "X2") (pin "38") (pinfunction "S_38") (pintype "passive"))
    )
    (net (code "99") (name "unconnected-(X2AH-S-Pad4)") (class "Default")
      (node (ref "X2") (pin "4") (pinfunction "S_4") (pintype "passive"))
    )
    (net (code "100") (name "unconnected-(X2AJ-S-Pad41)") (class "Default")
      (node (ref "X2") (pin "41") (pinfunction "S_41") (pintype "passive"))
    )
    (net (code "101") (name "unconnected-(X2AK-S-Pad42)") (class "Default")
      (node (ref "X2") (pin "42") (pinfunction "S_42") (pintype "passive"))
    )
    (net (code "102") (name "unconnected-(X2AL-S-Pad43)") (class "Default")
      (node (ref "X2") (pin "43") (pinfunction "S_43") (pintype "passive"))
    )
    (net (code "103") (name "unconnected-(X2AN-S-Pad45)") (class "Default")
      (node (ref "X2") (pin "45") (pinfunction "S_45") (pintype "passive"))
    )
    (net (code "104") (name "unconnected-(X2AO-S-Pad46)") (class "Default")
      (node (ref "X2") (pin "46") (pinfunction "S_46") (pintype "passive"))
    )
    (net (code "105") (name "unconnected-(X2AP-S-Pad47)") (class "Default")
      (node (ref "X2") (pin "47") (pinfunction "S_47") (pintype "passive"))
    )
    (net (code "106") (name "unconnected-(X2AQ-S-Pad48)") (class "Default")
      (node (ref "X2") (pin "48") (pinfunction "S_48") (pintype "passive"))
    )
    (net (code "107") (name "unconnected-(X2AR-S-Pad49)") (class "Default")
      (node (ref "X2") (pin "49") (pinfunction "S_49") (pintype "passive"))
    )
    (net (code "108") (name "unconnected-(X2AS-S-Pad5)") (class "Default")
      (node (ref "X2") (pin "5") (pinfunction "S_5") (pintype "passive"))
    )
    (net (code "109") (name "unconnected-(X2AT-S-Pad50)") (class "Default")
      (node (ref "X2") (pin "50") (pinfunction "S_50") (pintype "passive"))
    )
    (net (code "110") (name "unconnected-(X2AU-S-Pad6)") (class "Default")
      (node (ref "X2") (pin "6") (pinfunction "S_6") (pintype "passive"))
    )
    (net (code "111") (name "unconnected-(X2AV-S-Pad7)") (class "Default")
      (node (ref "X2") (pin "7") (pinfunction "S_7") (pintype "passive"))
    )
    (net (code "112") (name "unconnected-(X2AW-S-Pad8)") (class "Default")
      (node (ref "X2") (pin "8") (pinfunction "S_8") (pintype "passive"))
    )
    (net (code "113") (name "unconnected-(X2AX-S-Pad9)") (class "Default")
      (node (ref "X2") (pin "9") (pinfunction "S_9") (pintype "passive"))
    )
    (net (code "114") (name "unconnected-(X2B-S-Pad10)") (class "Default")
      (node (ref "X2") (pin "10") (pinfunction "S_10") (pintype "passive"))
    )
    (net (code "115") (name "unconnected-(X2C-S-Pad11)") (class "Default")
      (node (ref "X2") (pin "11") (pinfunction "S_11") (pintype "passive"))
    )
    (net (code "116") (name "unconnected-(X2D-S-Pad12)") (class "Default")
      (node (ref "X2") (pin "12") (pinfunction "S_12") (pintype "passive"))
    )
    (net (code "117") (name "unconnected-(X2E-S-Pad13)") (class "Default")
      (node (ref "X2") (pin "13") (pinfunction "S_13") (pintype "passive"))
    )
    (net (code "118") (name "unconnected-(X2F-S-Pad14)") (class "Default")
      (node (ref "X2") (pin "14") (pinfunction "S_14") (pintype "passive"))
    )
    (net (code "119") (name "unconnected-(X2G-S-Pad15)") (class "Default")
      (node (ref "X2") (pin "15") (pinfunction "S_15") (pintype "passive"))
    )
    (net (code "120") (name "unconnected-(X2H-S-Pad16)") (class "Default")
      (node (ref "X2") (pin "16") (pinfunction "S_16") (pintype "passive"))
    )
    (net (code "121") (name "unconnected-(X2I-S-Pad17)") (class "Default")
      (node (ref "X2") (pin "17") (pinfunction "S_17") (pintype "passive"))
    )
    (net (code "122") (name "unconnected-(X2J-S-Pad18)") (class "Default")
      (node (ref "X2") (pin "18") (pinfunction "S_18") (pintype "passive"))
    )
    (net (code "123") (name "unconnected-(X2K-S-Pad19)") (class "Default")
      (node (ref "X2") (pin "19") (pinfunction "S_19") (pintype "passive"))
    )
    (net (code "124") (name "unconnected-(X2L-S-Pad2)") (class "Default")
      (node (ref "X2") (pin "2") (pinfunction "S_2") (pintype "passive"))
    )
    (net (code "125") (name "unconnected-(X2T-S-Pad27)") (class "Default")
      (node (ref "X2") (pin "27") (pinfunction "S_27") (pintype "passive"))
    )
    (net (code "126") (name "unconnected-(X2U-S-Pad28)") (class "Default")
      (node (ref "X2") (pin "28") (pinfunction "S_28") (pintype "passive"))
    )
    (net (code "127") (name "unconnected-(X2W-S-Pad3)") (class "Default")
      (node (ref "X2") (pin "3") (pinfunction "S_3") (pintype "passive"))
    )
    (net (code "128") (name "unconnected-(X2Y-S-Pad31)") (class "Default")
      (node (ref "X2") (pin "31") (pinfunction "S_31") (pintype "passive"))
    )
    (net (code "129") (name "unconnected-(X2Z-S-Pad32)") (class "Default")
      (node (ref "X2") (pin "32") (pinfunction "S_32") (pintype "passive"))
    )
  )
)
